# Button.net
KiCad netlist of a schematic drawn in Altium Designer
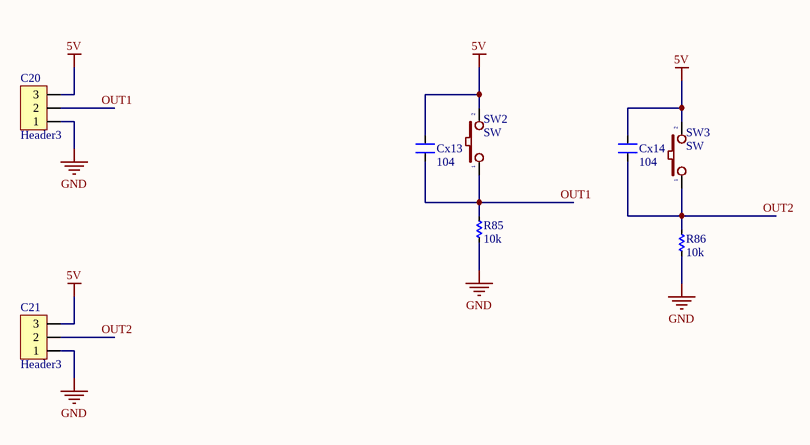
[diagram p0: Button.SchDoc]

(export (version "E")
  (design (tool "Eeschema 10.0.6"))
  (components
    (comp (ref "C20")
      (value "Header3")
      (footprint "Header3")
      (description "Header IDC, 3 x 1 Pin Vertical 2.54mm Pitch (Non-Boxed, Male)")
      (fields
        (field (name "MANUFACTURER") "Würth Elektronik eiSos GmbH")
        (field (name "PARTNO") "613002143121")
        (field (name "CREATED BY") "Karrer Zheng")
      )
      (libsource (lib "LIBRARY") (part "Header3"))
    )
    (comp (ref "C21")
      (value "Header3")
      (footprint "Header3")
      (description "Header IDC, 3 x 1 Pin Vertical 2.54mm Pitch (Non-Boxed, Male)")
      (fields
        (field (name "MANUFACTURER") "Würth Elektronik eiSos GmbH")
        (field (name "PARTNO") "613002143121")
        (field (name "CREATED BY") "Karrer Zheng")
      )
      (libsource (lib "LIBRARY") (part "Header3"))
    )
    (comp (ref "Cx13") (value "104") (footprint "CN-SMD-0805") (libsource (lib "LIBRARY") (part "CN")))
    (comp (ref "Cx14") (value "104") (footprint "CN-SMD-0805") (libsource (lib "LIBRARY") (part "CN")))
    (comp (ref "R85")
      (value "10k")
      (footprint "RES-SMD-0805")
      (description "Resistor")
      (fields
        (field (name "MANUFACTURER") "Generic Components")
        (field (name "PUBLISHER") "Altium Hobart Technology Centre")
      )
      (libsource (lib "LIBRARY") (part "Res-SMD"))
    )
    (comp (ref "R86")
      (value "10k")
      (footprint "RES-SMD-0805")
      (description "Resistor")
      (fields
        (field (name "MANUFACTURER") "Generic Components")
        (field (name "PUBLISHER") "Altium Hobart Technology Centre")
      )
      (libsource (lib "LIBRARY") (part "Res-SMD"))
    )
    (comp (ref "SW2")
      (value "SW")
      (footprint "SW1-SMD")
      (description "Switch button 2 pin")
      (libsource (lib "LIBRARY") (part "SW2"))
    )
    (comp (ref "SW3")
      (value "SW")
      (footprint "SW1-SMD")
      (description "Switch button 2 pin")
      (libsource (lib "LIBRARY") (part "SW2"))
    )
  )
  (nets
    (net (code "1") (name "/OUT1") (class "Default")
      (node (ref "C20") (pin "2") (pinfunction "2_2") (pintype "passive"))
      (node (ref "Cx13") (pin "1") (pinfunction "1_1") (pintype "passive"))
      (node (ref "R85") (pin "1") (pinfunction "1_1") (pintype "passive"))
      (node (ref "SW2") (pin "1") (pinfunction "1_1") (pintype "passive"))
    )
    (net (code "2") (name "/OUT2") (class "Default")
      (node (ref "C21") (pin "2") (pinfunction "2_2") (pintype "passive"))
      (node (ref "Cx14") (pin "1") (pinfunction "1_1") (pintype "passive"))
      (node (ref "R86") (pin "1") (pinfunction "1_1") (pintype "passive"))
      (node (ref "SW3") (pin "1") (pinfunction "1_1") (pintype "passive"))
    )
    (net (code "3") (name "5V") (class "Default")
      (node (ref "C20") (pin "3") (pinfunction "3_3") (pintype "passive"))
      (node (ref "C21") (pin "3") (pinfunction "3_3") (pintype "passive"))
      (node (ref "Cx13") (pin "2") (pinfunction "2_2") (pintype "passive"))
      (node (ref "Cx14") (pin "2") (pinfunction "2_2") (pintype "passive"))
      (node (ref "SW2") (pin "2") (pinfunction "2_2") (pintype "passive"))
      (node (ref "SW3") (pin "2") (pinfunction "2_2") (pintype "passive"))
    )
    (net (code "4") (name "GND") (class "Default")
      (node (ref "C20") (pin "1") (pinfunction "1_1") (pintype "passive"))
      (node (ref "C21") (pin "1") (pinfunction "1_1") (pintype "passive"))
      (node (ref "R85") (pin "2") (pinfunction "2_2") (pintype "passive"))
      (node (ref "R86") (pin "2") (pinfunction "2_2") (pintype "passive"))
    )
  )
)
